# LEDDistortionV2.net
KiCad netlist of a schematic drawn in EAGLE
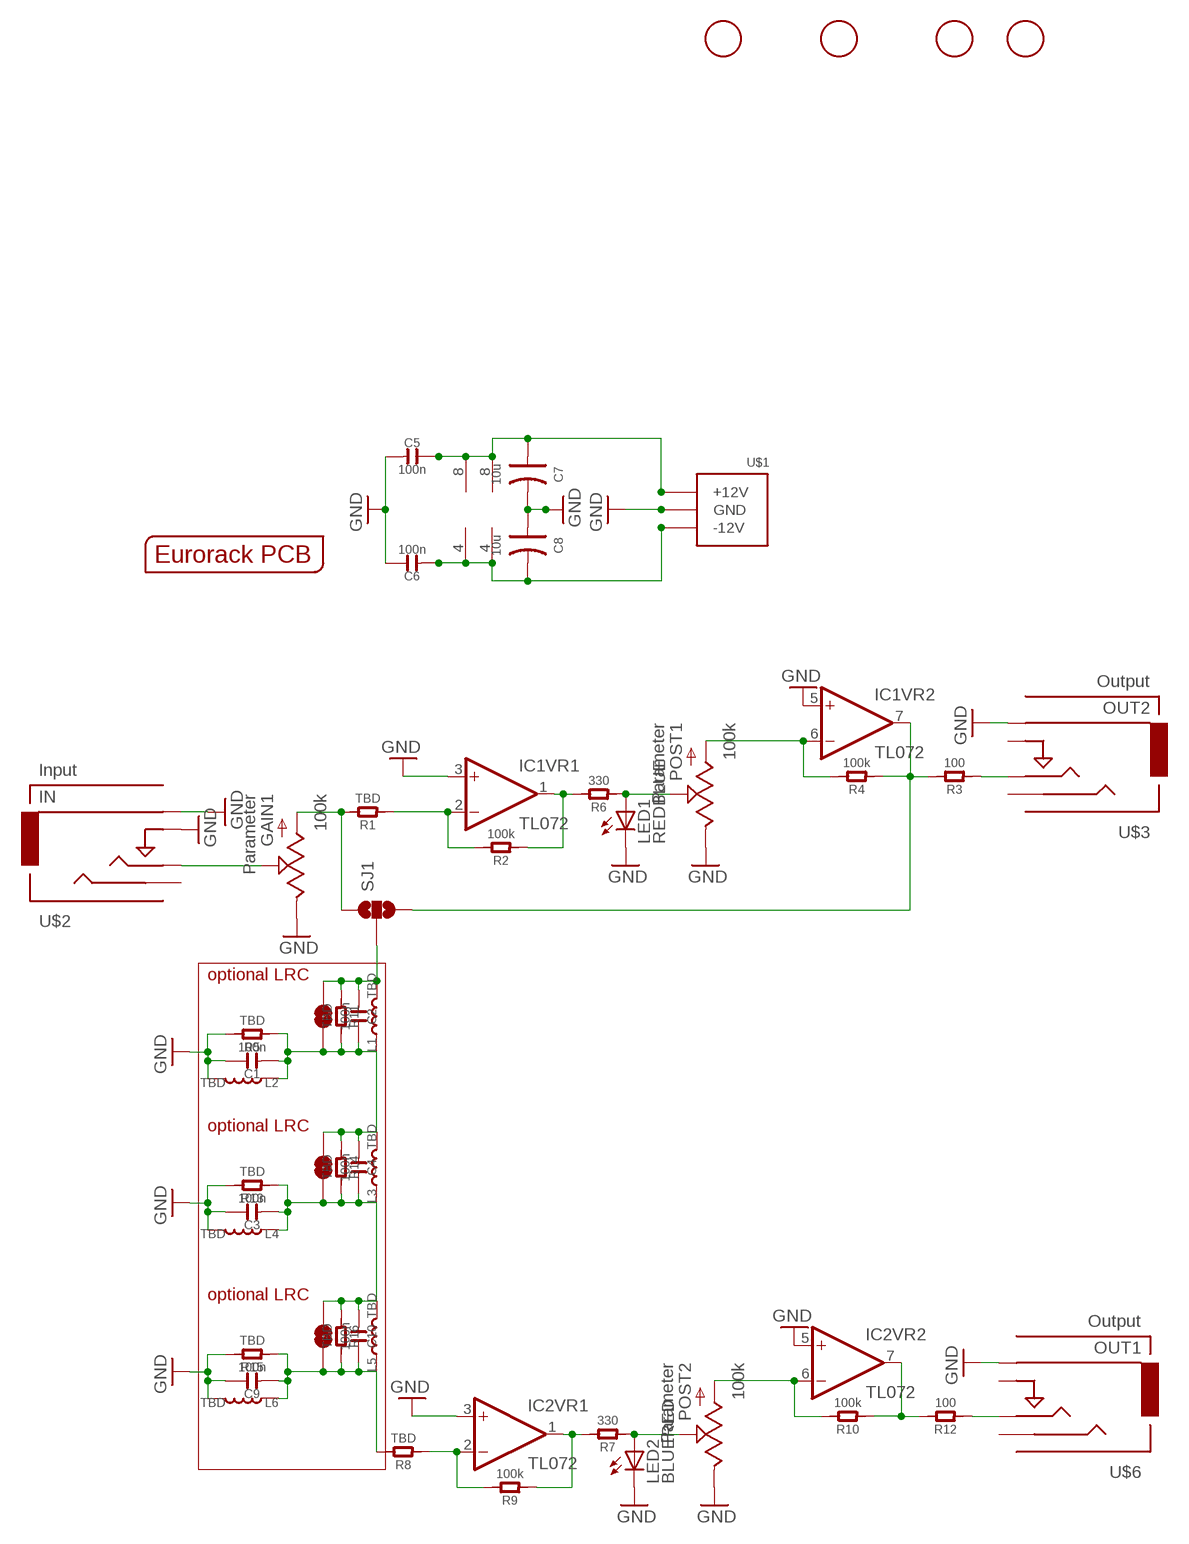
[diagram p0: schematic, sheet 1]

(export (version "E")
  (design (tool "Eeschema 10.0.6"))
  (components
    (comp (ref "C1")
      (value "100n")
      (footprint "eagle-import:C0805")
      (libsource (lib "eagle-import") (part "C-0805"))
    )
    (comp (ref "C2")
      (value "100n")
      (footprint "eagle-import:C0805")
      (libsource (lib "eagle-import") (part "C-0805"))
    )
    (comp (ref "C3")
      (value "100n")
      (footprint "eagle-import:C0805")
      (libsource (lib "eagle-import") (part "C-0805"))
    )
    (comp (ref "C4")
      (value "100n")
      (footprint "eagle-import:C0805")
      (libsource (lib "eagle-import") (part "C-0805"))
    )
    (comp (ref "C5")
      (value "100n")
      (footprint "eagle-import:C0805")
      (libsource (lib "eagle-import") (part "C-0805"))
    )
    (comp (ref "C6")
      (value "100n")
      (footprint "eagle-import:C0805")
      (libsource (lib "eagle-import") (part "C-0805"))
    )
    (comp (ref "C7")
      (value "10u")
      (footprint "eagle-import:AVX-A")
      (libsource (lib "eagle-import") (part "C-POLAR-A"))
    )
    (comp (ref "C8")
      (value "10u")
      (footprint "eagle-import:AVX-A")
      (libsource (lib "eagle-import") (part "C-POLAR-A"))
    )
    (comp (ref "C9")
      (value "100n")
      (footprint "eagle-import:C0805")
      (libsource (lib "eagle-import") (part "C-0805"))
    )
    (comp (ref "C10")
      (value "100n")
      (footprint "eagle-import:C0805")
      (libsource (lib "eagle-import") (part "C-0805"))
    )
    (comp (ref "GAIN1")
      (value "100k")
      (footprint "eagle-import:OG-POTS_ALPS_POT_VERTICAL")
      (libsource (lib "eagle-import") (part "POTZEPHPOT"))
    )
    (comp (ref "IC1")
      (value "TL072")
      (footprint "eagle-import:SO08")
      (libsource (lib "eagle-import") (part "TL072"))
    )
    (comp (ref "IC2")
      (value "TL072")
      (footprint "eagle-import:SO08")
      (libsource (lib "eagle-import") (part "TL072"))
    )
    (comp (ref "L1")
      (value "TBD")
      (footprint "eagle-import:L0420")
      (libsource (lib "eagle-import") (part "L-SPD3D16-4R7M"))
    )
    (comp (ref "L2")
      (value "TBD")
      (footprint "eagle-import:L0420")
      (libsource (lib "eagle-import") (part "L-SPD3D16-4R7M"))
    )
    (comp (ref "L3")
      (value "TBD")
      (footprint "eagle-import:L0420")
      (libsource (lib "eagle-import") (part "L-SPD3D16-4R7M"))
    )
    (comp (ref "L4")
      (value "TBD")
      (footprint "eagle-import:L0420")
      (libsource (lib "eagle-import") (part "L-SPD3D16-4R7M"))
    )
    (comp (ref "L5")
      (value "TBD")
      (footprint "eagle-import:L0420")
      (libsource (lib "eagle-import") (part "L-SPD3D16-4R7M"))
    )
    (comp (ref "L6")
      (value "TBD")
      (footprint "eagle-import:L0420")
      (libsource (lib "eagle-import") (part "L-SPD3D16-4R7M"))
    )
    (comp (ref "LED1")
      (value "REDBLUE")
      (footprint "eagle-import:LED3MM")
      (libsource (lib "eagle-import") (part "LED3MM"))
    )
    (comp (ref "LED2")
      (value "BLUERED")
      (footprint "eagle-import:LED3MM")
      (libsource (lib "eagle-import") (part "LED3MM"))
    )
    (comp (ref "POST1")
      (value "100k")
      (footprint "eagle-import:OG-POTS_ALPS_POT_VERTICAL")
      (libsource (lib "eagle-import") (part "POTZEPHPOT"))
    )
    (comp (ref "POST2")
      (value "100k")
      (footprint "eagle-import:OG-POTS_ALPS_POT_VERTICAL")
      (libsource (lib "eagle-import") (part "POTZEPHPOT"))
    )
    (comp (ref "R1")
      (value "TBD")
      (footprint "eagle-import:C0805")
      (libsource (lib "eagle-import") (part "R"))
    )
    (comp (ref "R2")
      (value "100k")
      (footprint "eagle-import:C0805")
      (libsource (lib "eagle-import") (part "R"))
    )
    (comp (ref "R3")
      (value "100")
      (footprint "eagle-import:C0805")
      (libsource (lib "eagle-import") (part "R"))
    )
    (comp (ref "R4")
      (value "100k")
      (footprint "eagle-import:C0805")
      (libsource (lib "eagle-import") (part "R"))
    )
    (comp (ref "R5")
      (value "TBD")
      (footprint "eagle-import:C0805")
      (libsource (lib "eagle-import") (part "R"))
    )
    (comp (ref "R6")
      (value "330")
      (footprint "eagle-import:C0805")
      (libsource (lib "eagle-import") (part "R"))
    )
    (comp (ref "R7")
      (value "330")
      (footprint "eagle-import:C0805")
      (libsource (lib "eagle-import") (part "R"))
    )
    (comp (ref "R8")
      (value "TBD")
      (footprint "eagle-import:C0805")
      (libsource (lib "eagle-import") (part "R"))
    )
    (comp (ref "R9")
      (value "100k")
      (footprint "eagle-import:C0805")
      (libsource (lib "eagle-import") (part "R"))
    )
    (comp (ref "R10")
      (value "100k")
      (footprint "eagle-import:C0805")
      (libsource (lib "eagle-import") (part "R"))
    )
    (comp (ref "R11")
      (value "TBD")
      (footprint "eagle-import:C0805")
      (libsource (lib "eagle-import") (part "R"))
    )
    (comp (ref "R12")
      (value "100")
      (footprint "eagle-import:C0805")
      (libsource (lib "eagle-import") (part "R"))
    )
    (comp (ref "R13")
      (value "TBD")
      (footprint "eagle-import:C0805")
      (libsource (lib "eagle-import") (part "R"))
    )
    (comp (ref "R14")
      (value "TBD")
      (footprint "eagle-import:C0805")
      (libsource (lib "eagle-import") (part "R"))
    )
    (comp (ref "R15")
      (value "TBD")
      (footprint "eagle-import:C0805")
      (libsource (lib "eagle-import") (part "R"))
    )
    (comp (ref "R16")
      (value "TBD")
      (footprint "eagle-import:C0805")
      (libsource (lib "eagle-import") (part "R"))
    )
    (comp (ref "SJ1")
      (value "SOLDERJUMPER_2WAYPASTE1&2")
      (footprint "eagle-import:SJ_3_PASTE1&2")
      (libsource (lib "eagle-import") (part "SOLDERJUMPER_2WAYPASTE1&2"))
    )
    (comp (ref "SJ2")
      (value "SOLDERJUMPERNC")
      (footprint "eagle-import:SJ_2S")
      (libsource (lib "eagle-import") (part "SOLDERJUMPERNC"))
    )
    (comp (ref "SJ3")
      (value "SOLDERJUMPERNC")
      (footprint "eagle-import:SJ_2S")
      (libsource (lib "eagle-import") (part "SOLDERJUMPERNC"))
    )
    (comp (ref "SJ4")
      (value "SOLDERJUMPERNC")
      (footprint "eagle-import:SJ_2S")
      (libsource (lib "eagle-import") (part "SOLDERJUMPERNC"))
    )
    (comp (ref "U$1")
      (value "POWER_SIMPLE10")
      (footprint "eagle-import:POWER_10")
      (libsource (lib "eagle-import") (part "POWER_SIMPLE10"))
    )
    (comp (ref "U$2")
      (value "IN")
      (footprint "eagle-import:3.5MM-JACK-SWITCH-13MM-INPUT")
      (fields (field (name "MPN") "PJ-341"))
      (libsource (lib "eagle-import") (part "AUDIO-JACKINPUT"))
    )
    (comp (ref "U$3")
      (value "OUT2")
      (footprint "eagle-import:3.5MM-JACK-SWITCH-13MM-OUTPUT")
      (fields (field (name "MPN") "PJ-341"))
      (libsource (lib "eagle-import") (part "AUDIO-JACKOUTPUT"))
    )
    (comp (ref "U$4")
      (value "EURORACK_PCB4HP")
      (footprint "eagle-import:EURORACK4HPPCB")
      (libsource (lib "eagle-import") (part "EURORACK_PCB4HP"))
    )
    (comp (ref "U$5")
      (value "FIDUCIAL")
      (footprint "eagle-import:FIDUCIAL_1MM")
      (libsource (lib "eagle-import") (part "FIDUCIAL"))
    )
    (comp (ref "U$6")
      (value "OUT1")
      (footprint "eagle-import:3.5MM-JACK-SWITCH-13MM-OUTPUT")
      (fields (field (name "MPN") "PJ-341"))
      (libsource (lib "eagle-import") (part "AUDIO-JACKOUTPUT"))
    )
    (comp (ref "U$7")
      (value "FIDUCIAL")
      (footprint "eagle-import:FIDUCIAL_1MM")
      (libsource (lib "eagle-import") (part "FIDUCIAL"))
    )
    (comp (ref "U$8")
      (value "FIDUCIAL")
      (footprint "eagle-import:FIDUCIAL_1MM")
      (libsource (lib "eagle-import") (part "FIDUCIAL"))
    )
    (comp (ref "U$9")
      (value "FIDUCIAL")
      (footprint "eagle-import:FIDUCIAL_1MM")
      (libsource (lib "eagle-import") (part "FIDUCIAL"))
    )
  )
  (nets
    (net (code "1") (name "GND") (class "Default")
      (node (ref "C1") (pin "2") (pinfunction "2_2") (pintype "bidirectional"))
      (node (ref "C3") (pin "2") (pinfunction "2_2") (pintype "bidirectional"))
      (node (ref "C5") (pin "1") (pinfunction "1_1") (pintype "bidirectional"))
      (node (ref "C6") (pin "2") (pinfunction "2_2") (pintype "bidirectional"))
      (node (ref "C7") (pin "-") (pinfunction "2_-") (pintype "bidirectional"))
      (node (ref "C8") (pin "+") (pinfunction "1_+") (pintype "bidirectional"))
      (node (ref "C9") (pin "2") (pinfunction "2_2") (pintype "bidirectional"))
      (node (ref "GAIN1") (pin "P$1") (pinfunction "E_P$1") (pintype "passive"))
      (node (ref "IC1") (pin "3") (pinfunction "+IN_3") (pintype "input"))
      (node (ref "IC1") (pin "5") (pinfunction "+IN_5") (pintype "input"))
      (node (ref "IC2") (pin "3") (pinfunction "+IN_3") (pintype "input"))
      (node (ref "IC2") (pin "5") (pinfunction "+IN_5") (pintype "input"))
      (node (ref "L2") (pin "2") (pinfunction "2_2") (pintype "passive"))
      (node (ref "L4") (pin "2") (pinfunction "2_2") (pintype "passive"))
      (node (ref "L6") (pin "2") (pinfunction "2_2") (pintype "passive"))
      (node (ref "LED1") (pin "K") (pinfunction "C_K") (pintype "passive"))
      (node (ref "LED2") (pin "K") (pinfunction "C_K") (pintype "passive"))
      (node (ref "POST1") (pin "P$1") (pinfunction "E_P$1") (pintype "passive"))
      (node (ref "POST2") (pin "P$1") (pinfunction "E_P$1") (pintype "passive"))
      (node (ref "R13") (pin "2") (pinfunction "2_2") (pintype "bidirectional"))
      (node (ref "R15") (pin "2") (pinfunction "2_2") (pintype "bidirectional"))
      (node (ref "R5") (pin "2") (pinfunction "2_2") (pintype "bidirectional"))
      (node (ref "U$1") (pin "3") (pinfunction "GND_3") (pintype "bidirectional"))
      (node (ref "U$1") (pin "4") (pinfunction "GND_4") (pintype "bidirectional"))
      (node (ref "U$1") (pin "5") (pinfunction "GND_5") (pintype "bidirectional"))
      (node (ref "U$1") (pin "6") (pinfunction "GND_6") (pintype "bidirectional"))
      (node (ref "U$1") (pin "7") (pinfunction "GND_7") (pintype "bidirectional"))
      (node (ref "U$1") (pin "8") (pinfunction "GND_8") (pintype "bidirectional"))
      (node (ref "U$2") (pin "RING@3") (pinfunction "RING_RING@3") (pintype "bidirectional"))
      (node (ref "U$2") (pin "SWITCH@3") (pinfunction "SWITCH_SWITCH@3") (pintype "bidirectional"))
      (node (ref "U$3") (pin "RING@3") (pinfunction "RING_RING@3") (pintype "bidirectional"))
      (node (ref "U$6") (pin "RING@3") (pinfunction "RING_RING@3") (pintype "bidirectional"))
    )
    (net (code "2") (name "Net-(C1-Pad1)") (class "Default")
      (node (ref "C1") (pin "1") (pinfunction "1_1") (pintype "bidirectional"))
      (node (ref "C2") (pin "2") (pinfunction "2_2") (pintype "bidirectional"))
      (node (ref "C4") (pin "1") (pinfunction "1_1") (pintype "bidirectional"))
      (node (ref "L1") (pin "1") (pinfunction "1_1") (pintype "passive"))
      (node (ref "L2") (pin "1") (pinfunction "1_1") (pintype "passive"))
      (node (ref "L3") (pin "2") (pinfunction "2_2") (pintype "passive"))
      (node (ref "R11") (pin "2") (pinfunction "2_2") (pintype "bidirectional"))
      (node (ref "R14") (pin "1") (pinfunction "1_1") (pintype "bidirectional"))
      (node (ref "R5") (pin "1") (pinfunction "1_1") (pintype "bidirectional"))
      (node (ref "SJ2") (pin "1") (pinfunction "1_1") (pintype "passive"))
      (node (ref "SJ3") (pin "2") (pinfunction "2_2") (pintype "passive"))
    )
    (net (code "3") (name "Net-(C2-Pad1)") (class "Default")
      (node (ref "C2") (pin "1") (pinfunction "1_1") (pintype "bidirectional"))
      (node (ref "L1") (pin "2") (pinfunction "2_2") (pintype "passive"))
      (node (ref "R11") (pin "1") (pinfunction "1_1") (pintype "bidirectional"))
      (node (ref "SJ1") (pin "2") (pinfunction "2_2") (pintype "passive"))
      (node (ref "SJ2") (pin "2") (pinfunction "2_2") (pintype "passive"))
    )
    (net (code "4") (name "Net-(C7-1)") (class "Default")
      (node (ref "C5") (pin "2") (pinfunction "2_2") (pintype "bidirectional"))
      (node (ref "C7") (pin "+") (pinfunction "1_+") (pintype "bidirectional"))
      (node (ref "IC1") (pin "8") (pinfunction "V+_8") (pintype "power_in"))
      (node (ref "IC2") (pin "8") (pinfunction "V+_8") (pintype "power_in"))
      (node (ref "U$1") (pin "10") (pinfunction "+12V_10") (pintype "bidirectional"))
      (node (ref "U$1") (pin "9") (pinfunction "+12V_9") (pintype "bidirectional"))
    )
    (net (code "5") (name "Net-(C8-2)") (class "Default")
      (node (ref "C6") (pin "1") (pinfunction "1_1") (pintype "bidirectional"))
      (node (ref "C8") (pin "-") (pinfunction "2_-") (pintype "bidirectional"))
      (node (ref "IC1") (pin "4") (pinfunction "V-_4") (pintype "power_in"))
      (node (ref "IC2") (pin "4") (pinfunction "V-_4") (pintype "power_in"))
      (node (ref "U$1") (pin "1") (pinfunction "-12V_1") (pintype "bidirectional"))
      (node (ref "U$1") (pin "2") (pinfunction "-12V_2") (pintype "bidirectional"))
    )
    (net (code "6") (name "Net-(C10-Pad1)") (class "Default")
      (node (ref "C10") (pin "1") (pinfunction "1_1") (pintype "bidirectional"))
      (node (ref "C3") (pin "1") (pinfunction "1_1") (pintype "bidirectional"))
      (node (ref "C4") (pin "2") (pinfunction "2_2") (pintype "bidirectional"))
      (node (ref "L3") (pin "1") (pinfunction "1_1") (pintype "passive"))
      (node (ref "L4") (pin "1") (pinfunction "1_1") (pintype "passive"))
      (node (ref "L5") (pin "2") (pinfunction "2_2") (pintype "passive"))
      (node (ref "R13") (pin "1") (pinfunction "1_1") (pintype "bidirectional"))
      (node (ref "R14") (pin "2") (pinfunction "2_2") (pintype "bidirectional"))
      (node (ref "R16") (pin "1") (pinfunction "1_1") (pintype "bidirectional"))
      (node (ref "SJ3") (pin "1") (pinfunction "1_1") (pintype "passive"))
      (node (ref "SJ4") (pin "2") (pinfunction "2_2") (pintype "passive"))
    )
    (net (code "7") (name "Net-(C10-Pad2)") (class "Default")
      (node (ref "C10") (pin "2") (pinfunction "2_2") (pintype "bidirectional"))
      (node (ref "C9") (pin "1") (pinfunction "1_1") (pintype "bidirectional"))
      (node (ref "L5") (pin "1") (pinfunction "1_1") (pintype "passive"))
      (node (ref "L6") (pin "1") (pinfunction "1_1") (pintype "passive"))
      (node (ref "R15") (pin "1") (pinfunction "1_1") (pintype "bidirectional"))
      (node (ref "R16") (pin "2") (pinfunction "2_2") (pintype "bidirectional"))
      (node (ref "R8") (pin "2") (pinfunction "2_2") (pintype "bidirectional"))
      (node (ref "SJ4") (pin "1") (pinfunction "1_1") (pintype "passive"))
    )
    (net (code "8") (name "Net-(GAIN1-A)") (class "Default")
      (node (ref "GAIN1") (pin "P$3") (pinfunction "A_P$3") (pintype "passive"))
      (node (ref "R1") (pin "2") (pinfunction "2_2") (pintype "bidirectional"))
      (node (ref "SJ1") (pin "1") (pinfunction "1_1") (pintype "passive"))
    )
    (net (code "9") (name "Net-(GAIN1-S)") (class "Default")
      (node (ref "GAIN1") (pin "P$2") (pinfunction "S_P$2") (pintype "passive"))
      (node (ref "U$2") (pin "TIP@3") (pinfunction "TIP_TIP@3") (pintype "bidirectional"))
    )
    (net (code "10") (name "Net-(IC1A--IN)") (class "Default")
      (node (ref "IC1") (pin "2") (pinfunction "-IN_2") (pintype "input"))
      (node (ref "R1") (pin "1") (pinfunction "1_1") (pintype "bidirectional"))
      (node (ref "R2") (pin "2") (pinfunction "2_2") (pintype "bidirectional"))
    )
    (net (code "11") (name "Net-(IC1A-OUT)") (class "Default")
      (node (ref "IC1") (pin "1") (pinfunction "OUT_1") (pintype "output"))
      (node (ref "R2") (pin "1") (pinfunction "1_1") (pintype "bidirectional"))
      (node (ref "R6") (pin "2") (pinfunction "2_2") (pintype "bidirectional"))
    )
    (net (code "12") (name "Net-(IC1B--IN)") (class "Default")
      (node (ref "IC1") (pin "6") (pinfunction "-IN_6") (pintype "input"))
      (node (ref "POST1") (pin "P$3") (pinfunction "A_P$3") (pintype "passive"))
      (node (ref "R4") (pin "2") (pinfunction "2_2") (pintype "bidirectional"))
    )
    (net (code "13") (name "Net-(IC1B-OUT)") (class "Default")
      (node (ref "IC1") (pin "7") (pinfunction "OUT_7") (pintype "output"))
      (node (ref "R3") (pin "2") (pinfunction "2_2") (pintype "bidirectional"))
      (node (ref "R4") (pin "1") (pinfunction "1_1") (pintype "bidirectional"))
      (node (ref "SJ1") (pin "3") (pinfunction "3_3") (pintype "passive"))
    )
    (net (code "14") (name "Net-(IC2A--IN)") (class "Default")
      (node (ref "IC2") (pin "2") (pinfunction "-IN_2") (pintype "input"))
      (node (ref "R8") (pin "1") (pinfunction "1_1") (pintype "bidirectional"))
      (node (ref "R9") (pin "2") (pinfunction "2_2") (pintype "bidirectional"))
    )
    (net (code "15") (name "Net-(IC2A-OUT)") (class "Default")
      (node (ref "IC2") (pin "1") (pinfunction "OUT_1") (pintype "output"))
      (node (ref "R7") (pin "2") (pinfunction "2_2") (pintype "bidirectional"))
      (node (ref "R9") (pin "1") (pinfunction "1_1") (pintype "bidirectional"))
    )
    (net (code "16") (name "Net-(IC2B--IN)") (class "Default")
      (node (ref "IC2") (pin "6") (pinfunction "-IN_6") (pintype "input"))
      (node (ref "POST2") (pin "P$3") (pinfunction "A_P$3") (pintype "passive"))
      (node (ref "R10") (pin "2") (pinfunction "2_2") (pintype "bidirectional"))
    )
    (net (code "17") (name "Net-(IC2B-OUT)") (class "Default")
      (node (ref "IC2") (pin "7") (pinfunction "OUT_7") (pintype "output"))
      (node (ref "R10") (pin "1") (pinfunction "1_1") (pintype "bidirectional"))
      (node (ref "R12") (pin "2") (pinfunction "2_2") (pintype "bidirectional"))
    )
    (net (code "18") (name "Net-(POST1-S)") (class "Default")
      (node (ref "LED1") (pin "A") (pinfunction "A_A") (pintype "passive"))
      (node (ref "POST1") (pin "P$2") (pinfunction "S_P$2") (pintype "passive"))
      (node (ref "R6") (pin "1") (pinfunction "1_1") (pintype "bidirectional"))
    )
    (net (code "19") (name "Net-(POST2-S)") (class "Default")
      (node (ref "LED2") (pin "A") (pinfunction "A_A") (pintype "passive"))
      (node (ref "POST2") (pin "P$2") (pinfunction "S_P$2") (pintype "passive"))
      (node (ref "R7") (pin "1") (pinfunction "1_1") (pintype "bidirectional"))
    )
    (net (code "20") (name "Net-(U$3-TIP)") (class "Default")
      (node (ref "R3") (pin "1") (pinfunction "1_1") (pintype "bidirectional"))
      (node (ref "U$3") (pin "TIP@3") (pinfunction "TIP_TIP@3") (pintype "bidirectional"))
    )
    (net (code "21") (name "Net-(U$6-TIP)") (class "Default")
      (node (ref "R12") (pin "1") (pinfunction "1_1") (pintype "bidirectional"))
      (node (ref "U$6") (pin "TIP@3") (pinfunction "TIP_TIP@3") (pintype "bidirectional"))
    )
    (net (code "22") (name "unconnected-(U$2-SECOND-PadSECOND@3)") (class "Default")
      (node (ref "U$2") (pin "SECOND@3") (pinfunction "SECOND_SECOND@3") (pintype "bidirectional"))
    )
    (net (code "23") (name "unconnected-(U$3-SECOND-PadSECOND@3)") (class "Default")
      (node (ref "U$3") (pin "SECOND@3") (pinfunction "SECOND_SECOND@3") (pintype "bidirectional"))
    )
    (net (code "24") (name "unconnected-(U$3-SWITCH-PadSWITCH@3)") (class "Default")
      (node (ref "U$3") (pin "SWITCH@3") (pinfunction "SWITCH_SWITCH@3") (pintype "bidirectional"))
    )
    (net (code "25") (name "unconnected-(U$6-SECOND-PadSECOND@3)") (class "Default")
      (node (ref "U$6") (pin "SECOND@3") (pinfunction "SECOND_SECOND@3") (pintype "bidirectional"))
    )
    (net (code "26") (name "unconnected-(U$6-SWITCH-PadSWITCH@3)") (class "Default")
      (node (ref "U$6") (pin "SWITCH@3") (pinfunction "SWITCH_SWITCH@3") (pintype "bidirectional"))
    )
  )
)
